# Communication_Interfaces.net
KiCad netlist of a schematic drawn in Altium Designer
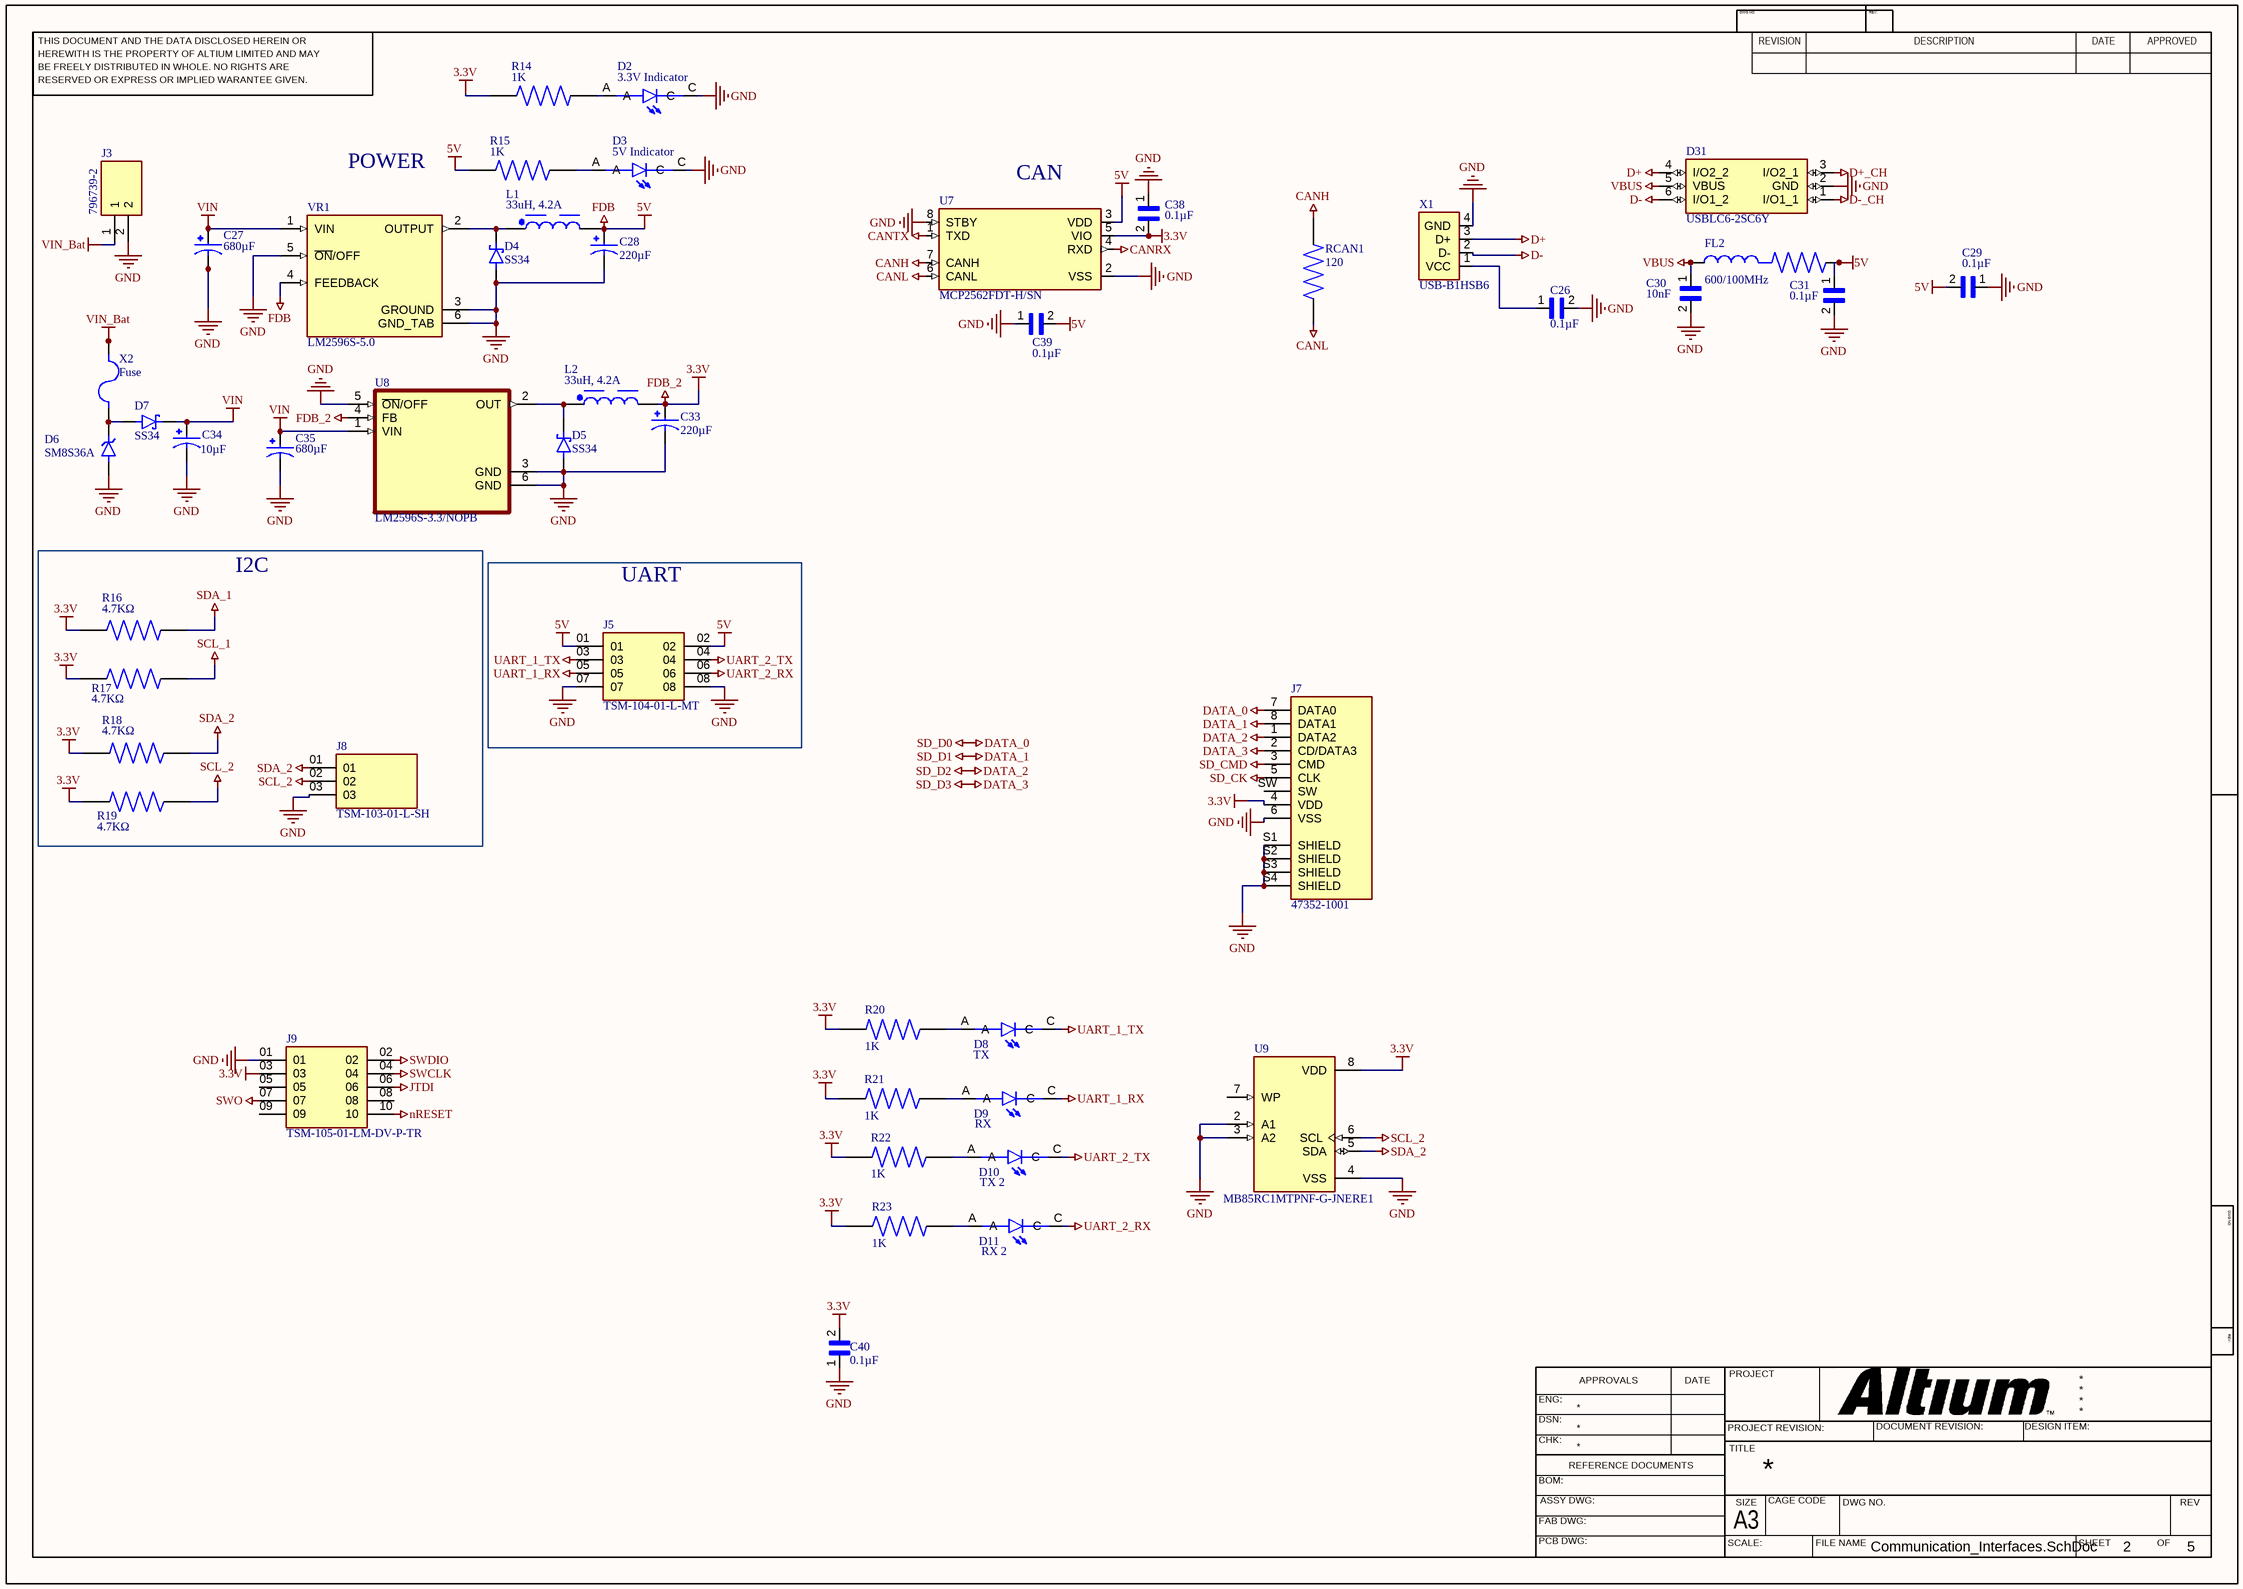
[diagram p0: Communication_Interfaces.SchDoc]

(export (version "E")
  (design (tool "Eeschema 10.0.6"))
  (components
    (comp (ref "C26")
      (value "0.1µF")
      (footprint "CAPC1608X90N")
      (description "Multilayer Ceramic Capacitors MLCC - SMD/SMT")
      (fields (field (name "MP") "06035C104MAZ2A"))
      (libsource (lib "06035C104MAZ2A") (part "06035C104MAZ2A"))
    )
    (comp (ref "C27")
      (value "680µF")
      (footprint "CAP_EEEFN1E681UV")
      (description "CAP ALUM 680UF 20% 25V SMD")
      (fields (field (name "MF") "Panasonic Electronic Components") (field (name "MP") "EEE-FN1E681UV"))
      (libsource (lib "") (part "EEEFN1E681UV_1"))
    )
    (comp (ref "C28")
      (value "220µF")
      (footprint "CAP_EEEFP1V221AV")
      (description "CAP ALUM 220UF 20% 35V SMD")
      (fields (field (name "MF") "Panasonic Electronic Components") (field (name "MP") "EEE-FP1V221AV"))
      (libsource (lib "EEEFP1V221AV") (part "EEEFP1V221AV"))
    )
    (comp (ref "C29")
      (value "0.1µF")
      (footprint "CAPC1608X90N")
      (description "Multilayer Ceramic Capacitors MLCC - SMD/SMT")
      (fields (field (name "MP") "06035C104MAZ2A"))
      (libsource (lib "") (part "06035C104MAZ2A_2"))
    )
    (comp (ref "C30")
      (value "10nF")
      (footprint "CAPC1608X90N")
      (description "Multilayer Ceramic Capacitors MLCC - SMD/SMT")
      (fields (field (name "MP") "06035C104MAZ2A"))
      (libsource (lib "") (part "06035C104MAZ2A_3"))
    )
    (comp (ref "C31")
      (value "0.1µF")
      (footprint "CAPC1608X90N")
      (description "Multilayer Ceramic Capacitors MLCC - SMD/SMT")
      (fields (field (name "MP") "06035C104MAZ2A"))
      (libsource (lib "") (part "06035C104MAZ2A_3"))
    )
    (comp (ref "C33")
      (value "220µF")
      (footprint "CAP_EEEFP1V221AV")
      (description "CAP ALUM 220UF 20% 35V SMD")
      (fields (field (name "MF") "Panasonic Electronic Components") (field (name "MP") "EEE-FP1V221AV"))
      (libsource (lib "") (part "EEEFP1V221AV_1"))
    )
    (comp (ref "C34")
      (value "10µF")
      (footprint "CAPPRD500W50D500H1100")
      (description "10ÂµF 25V Aluminum Electrolytic Capacitors Radial, Can 2000 Hrs @ 85Â°C")
      (fields (field (name "MF") "Panasonic") (field (name "MP") "ECEA1EN100UB"))
      (libsource (lib "ECEA1EN100UB") (part "ECEA1EN100UB"))
    )
    (comp (ref "C35")
      (value "680µF")
      (footprint "CAP_EEEFN1E681UV")
      (description "CAP ALUM 680UF 20% 25V SMD")
      (fields (field (name "MF") "Panasonic Electronic Components") (field (name "MP") "EEE-FN1E681UV"))
      (libsource (lib "EEEFN1E681UV") (part "EEEFN1E681UV"))
    )
    (comp (ref "C38")
      (value "0.1µF")
      (footprint "CAPC1608X90N")
      (description "Multilayer Ceramic Capacitors MLCC - SMD/SMT")
      (fields (field (name "MP") "06035C104MAZ2A"))
      (libsource (lib "") (part "06035C104MAZ2A_3"))
    )
    (comp (ref "C39")
      (value "0.1µF")
      (footprint "CAPC1608X90N")
      (description "Multilayer Ceramic Capacitors MLCC - SMD/SMT")
      (fields (field (name "MP") "06035C104MAZ2A"))
      (libsource (lib "06035C104MAZ2A") (part "06035C104MAZ2A"))
    )
    (comp (ref "C40")
      (value "0.1µF")
      (footprint "CAPC1608X90N")
      (description "Multilayer Ceramic Capacitors MLCC - SMD/SMT")
      (fields (field (name "MP") "06035C104MAZ2A"))
      (libsource (lib "") (part "06035C104MAZ2A_1"))
    )
    (comp (ref "D2")
      (value "3.3V Indicator")
      (footprint "LEDC2012X70N")
      (description "LED Uni-Color Green 4-Pin Chip 0805 T/R")
      (fields (field (name "MP") "597-3305-607F"))
      (libsource (lib "597-3305-607F") (part "597-3305-607F"))
    )
    (comp (ref "D3")
      (value "5V Indicator")
      (footprint "LEDC2012X70N")
      (description "LED Uni-Color Green 4-Pin Chip 0805 T/R")
      (fields (field (name "MP") "597-3305-607F"))
      (libsource (lib "597-3305-607F") (part "597-3305-607F"))
    )
    (comp (ref "D4")
      (value "SS34")
      (footprint "DIO_SS34")
      (description "3A, 40V, Schottky Rectifier")
      (fields (field (name "MF") "Taiwan Semiconductor"))
      (libsource (lib "SS34") (part "SS34"))
    )
    (comp (ref "D5")
      (value "SS34")
      (footprint "DIO_SS34")
      (description "3A, 40V, Schottky Rectifier")
      (fields (field (name "MF") "Taiwan Semiconductor"))
      (libsource (lib "SS34") (part "SS34"))
    )
    (comp (ref "D6")
      (value "SM8S36A")
      (footprint "TVSP_SM8S36A")
      (libsource (lib "SM8S36A") (part "SM8S36A"))
    )
    (comp (ref "D7")
      (value "SS34")
      (footprint "DIO_SS34")
      (description "3A, 40V, Schottky Rectifier")
      (fields (field (name "MF") "Taiwan Semiconductor"))
      (libsource (lib "SS34 (1)") (part "SS34"))
    )
    (comp (ref "D8")
      (value "TX")
      (footprint "LEDC2012X70N")
      (description "LED Uni-Color Green 4-Pin Chip 0805 T/R")
      (fields (field (name "MP") "597-3305-607F"))
      (libsource (lib "597-3305-607F") (part "597-3305-607F"))
    )
    (comp (ref "D9")
      (value "RX")
      (footprint "LEDC2012X70N")
      (description "LED Uni-Color Green 4-Pin Chip 0805 T/R")
      (fields (field (name "MP") "597-3305-607F"))
      (libsource (lib "597-3305-607F") (part "597-3305-607F"))
    )
    (comp (ref "D10")
      (value "TX 2")
      (footprint "LEDC2012X70N")
      (description "LED Uni-Color Green 4-Pin Chip 0805 T/R")
      (fields (field (name "MP") "597-3305-607F"))
      (libsource (lib "597-3305-607F") (part "597-3305-607F"))
    )
    (comp (ref "D11")
      (value "RX 2")
      (footprint "LEDC2012X70N")
      (description "LED Uni-Color Green 4-Pin Chip 0805 T/R")
      (fields (field (name "MP") "597-3305-607F"))
      (libsource (lib "597-3305-607F") (part "597-3305-607F"))
    )
    (comp (ref "D31")
      (value "USBLC6-2SC6Y")
      (footprint "SOT95P280X145-6N")
      (description "17V Clamp 5A (8/20µs) Ipp Tvs Diode Surface Mount SOT-23-6")
      (fields (field (name "MF") "STMicroelectronics"))
      (libsource (lib "USBLC6-2SC6Y") (part "USBLC6-2SC6Y"))
    )
    (comp (ref "FL2")
      (value "600/100MHz")
      (footprint "BEADC1608X95N")
      (description "600 Ohms @ 100MHz 1 Ferrite Bead 0603 _1608 Metric_ 700mA")
      (fields (field (name "MF") "Murata") (field (name "MP") "BLM18DN601SZ1D"))
      (libsource (lib "BLM18DN601SZ1DA") (part "BLM18DN601SZ1D"))
    )
    (comp (ref "J3")
      (value "796739-2")
      (footprint "TE_796739-2")
      (description "Conn Terminal Block F 2 POS 9.53mm Solder RA Thru-Hole 32A/Contact")
      (fields (field (name "MF") "TE Connectivity"))
      (libsource (lib "796739-2") (part "796739-2"))
    )
    (comp (ref "J5")
      (value "TSM-104-01-L-MT")
      (footprint "SAMTEC_TSM-104-01-L-MT")
      (description "TSM Series .100 Surface Mount Terminal Strip")
      (fields (field (name "MF") "Samtec"))
      (libsource (lib "TSM-104-01-L-MT") (part "TSM-104-01-L-MT"))
    )
    (comp (ref "J7")
      (value "47352-1001")
      (footprint "MOLEX_47352-1001")
      (description "8 (6 + 2) Position Card Connector Secure Digital - microSDâ„¢ Surface Mount, Right Angle Gold")
      (fields (field (name "MP") "473521001") (field (name "MF") "Molex"))
      (libsource (lib "47352-1001") (part "47352-1001"))
    )
    (comp (ref "J8")
      (value "TSM-103-01-L-SH")
      (footprint "SAMTEC_TSM-103-01-L-SH")
      (fields (field (name "MF") "Samtec Inc."))
      (libsource (lib "TSM-103-01-L-SH (1)") (part "TSM-103-01-L-SH"))
    )
    (comp (ref "J9")
      (value "TSM-105-01-LM-DV-P-TR")
      (footprint "SAMTEC_TSM-105-01-LM-DV-P-TR")
      (description "TSM - Samtec 2.54mm Dual Row Vertical Surface Mount Header 5.84mm Post Height (01) - Fast Stock")
      (fields (field (name "MF") "Samtec"))
      (libsource (lib "TSM-105-01-LM-DV-P-TR") (part "TSM-105-01-LM-DV-P-TR"))
    )
    (comp (ref "L1")
      (value "33uH, 4.2A")
      (footprint "WE-PD_1210")
      (description "WE-PD SMT Power Inductor, size 1210, 33uH, 4.2A, 45mOhm")
      (fields
        (field (name "MANUFACTURER PART NUMBER") "7447709330")
        (field (name "MANUFACTURER") "Wurth Elektronik")
      )
      (libsource (lib "Altium_WE-PD_rev22g") (part "7447709330"))
    )
    (comp (ref "L2")
      (value "33uH, 4.2A")
      (footprint "WE-PD_1210")
      (description "WE-PD SMT Power Inductor, size 1210, 33uH, 4.2A, 45mOhm")
      (fields
        (field (name "MANUFACTURER PART NUMBER") "7447709330")
        (field (name "MANUFACTURER") "Wurth Elektronik")
      )
      (libsource (lib "Altium_WE-PD_rev22g") (part "7447709330"))
    )
    (comp (ref "R14")
      (value "1K")
      (footprint "RESC3116X65N")
      (fields (field (name "MF") "Yageo Corporation") (field (name "MP") "RC1206JR071KL"))
      (libsource (lib "RC1206JR-071KL") (part "RC1206JR-071KL"))
    )
    (comp (ref "R15")
      (value "1K")
      (footprint "RESC3116X65N")
      (fields (field (name "MF") "Yageo Corporation") (field (name "MP") "RC1206JR071KL"))
      (libsource (lib "RC1206JR-071KL") (part "RC1206JR-071KL"))
    )
    (comp (ref "R16")
      (value "4.7KΩ")
      (footprint "RES_ERJS06J472V")
      (fields (field (name "MP") "ERJS06J472V"))
      (libsource (lib "ERJS06J472V") (part "ERJS06J472V"))
    )
    (comp (ref "R17")
      (value "4.7KΩ")
      (footprint "RES_ERJS06J472V")
      (fields (field (name "MP") "ERJS06J472V"))
      (libsource (lib "ERJS06J472V") (part "ERJS06J472V"))
    )
    (comp (ref "R18")
      (value "4.7KΩ")
      (footprint "RES_ERJS06J472V")
      (fields (field (name "MP") "ERJS06J472V"))
      (libsource (lib "ERJS06J472V") (part "ERJS06J472V"))
    )
    (comp (ref "R19")
      (value "4.7KΩ")
      (footprint "RES_ERJS06J472V")
      (fields (field (name "MP") "ERJS06J472V"))
      (libsource (lib "ERJS06J472V") (part "ERJS06J472V"))
    )
    (comp (ref "R20")
      (value "1K")
      (footprint "RESC3116X65N")
      (fields (field (name "MF") "Yageo Corporation") (field (name "MP") "RC1206JR071KL"))
      (libsource (lib "RC1206JR-071KL") (part "RC1206JR-071KL"))
    )
    (comp (ref "R21")
      (value "1K")
      (footprint "RESC3116X65N")
      (fields (field (name "MF") "Yageo Corporation") (field (name "MP") "RC1206JR071KL"))
      (libsource (lib "RC1206JR-071KL") (part "RC1206JR-071KL"))
    )
    (comp (ref "R22")
      (value "1K")
      (footprint "RESC3116X65N")
      (fields (field (name "MF") "Yageo Corporation") (field (name "MP") "RC1206JR071KL"))
      (libsource (lib "RC1206JR-071KL") (part "RC1206JR-071KL"))
    )
    (comp (ref "R23")
      (value "1K")
      (footprint "RESC3116X65N")
      (fields (field (name "MF") "Yageo Corporation") (field (name "MP") "RC1206JR071KL"))
      (libsource (lib "RC1206JR-071KL") (part "RC1206JR-071KL"))
    )
    (comp (ref "RCAN1")
      (value "120")
      (footprint "RESC3116X65N")
      (fields (field (name "MP") "AA1206JR-07470RL"))
      (libsource (lib "AA1206JR-07470RL") (part "AA1206JR-07470RL"))
    )
    (comp (ref "U7")
      (value "MCP2562FDT-H/SN")
      (footprint "SOIC127P600X175-8N")
      (description "CAN Flexible Data Rate Transceiver ¦ Microchip Technology Inc. MCP2562FDT-H/SN")
      (fields (field (name "MF") "Microchip"))
      (libsource (lib "MCP2562FDT-H_SN") (part "MCP2562FDT-H/SN"))
    )
    (comp (ref "U8")
      (value "LM2596S-3.3/NOPB")
      (footprint "VREG_LM2596S-3.3/NOPB")
      (libsource (lib "LM2596S-3.3_NOPB") (part "LM2596S-3.3/NOPB"))
    )
    (comp (ref "U9")
      (value "MB85RC1MTPNF-G-JNERE1")
      (footprint "SOIC127P600X175-8N")
      (description "FRAM _Ferroelectric RAM_ Memory IC 1Mb _128K x 8_ IÂ²C 3.4MHz 130ns 8-SOP")
      (fields (field (name "MF") "Fujitsu Electronics"))
      (libsource (lib "MB85RC1MTPNF-G-JNERE1") (part "MB85RC1MTPNF-G-JNERE1"))
    )
    (comp (ref "VR1")
      (value "LM2596S-5.0")
      (footprint "TO170P1524X483-6N")
      (description "SIMPLE SWITCHER&reg; 4.5V to 40V, 3A Low Component Count Step-Down Regulator")
      (fields (field (name "MP") "LM2596S-5.0/NOPB") (field (name "MF") "Texas Instruments"))
      (libsource (lib "LM2596S-5.0") (part "LM2596S-5.0"))
    )
    (comp (ref "X1")
      (value "USB-B1HSB6")
      (footprint "OST_USB-B1HSB6")
      (description "USB-B (USB TYPE-B) - Receptacle Connector 4 Position Through Hole, Right Angle")
      (fields (field (name "MF") "On Shore"))
      (libsource (lib "USB-B1HSB6") (part "USB-B1HSB6"))
    )
    (comp (ref "X2")
      (value "Fuse")
      (footprint "FUSE_3522-2")
      (fields (field (name "MF") "{'manufacturer': u'Keystone Electronics'}") (field (name "MP") "3522-2"))
      (libsource (lib "3522-2") (part "3522-2"))
    )
  )
  (nets
    (net (code "1") (name "3.3V") (class "Default")
      (node (ref "C33") (pin "1") (pinfunction "1_1") (pintype "passive"))
      (node (ref "C38") (pin "2") (pinfunction "2_2") (pintype "passive"))
      (node (ref "C40") (pin "2") (pinfunction "2_2") (pintype "passive"))
      (node (ref "J7") (pin "4") (pinfunction "VDD_4") (pintype "passive"))
      (node (ref "J9") (pin "03") (pinfunction "03_03") (pintype "passive"))
      (node (ref "L2") (pin "2") (pinfunction "2_2") (pintype "passive"))
      (node (ref "R14") (pin "1") (pinfunction "1_1") (pintype "passive"))
      (node (ref "R16") (pin "2") (pinfunction "2_2") (pintype "passive"))
      (node (ref "R17") (pin "1") (pinfunction "1_1") (pintype "passive"))
      (node (ref "R18") (pin "2") (pinfunction "2_2") (pintype "passive"))
      (node (ref "R19") (pin "1") (pinfunction "1_1") (pintype "passive"))
      (node (ref "R20") (pin "1") (pinfunction "1_1") (pintype "passive"))
      (node (ref "R21") (pin "1") (pinfunction "1_1") (pintype "passive"))
      (node (ref "R22") (pin "1") (pinfunction "1_1") (pintype "passive"))
      (node (ref "R23") (pin "1") (pinfunction "1_1") (pintype "passive"))
      (node (ref "U7") (pin "5") (pinfunction "VIO_5") (pintype "power_in"))
      (node (ref "U8") (pin "4") (pinfunction "FB_4") (pintype "input"))
      (node (ref "U9") (pin "8") (pinfunction "VDD_8") (pintype "power_in"))
    )
    (net (code "2") (name "5V") (class "Default")
      (node (ref "C28") (pin "1") (pinfunction "1_1") (pintype "passive"))
      (node (ref "C29") (pin "2") (pinfunction "2_2") (pintype "passive"))
      (node (ref "C31") (pin "1") (pinfunction "1_1") (pintype "passive"))
      (node (ref "C39") (pin "2") (pinfunction "2_2") (pintype "passive"))
      (node (ref "FL2") (pin "2") (pinfunction "2_2") (pintype "passive"))
      (node (ref "J5") (pin "01") (pinfunction "01_01") (pintype "passive"))
      (node (ref "J5") (pin "02") (pinfunction "02_02") (pintype "passive"))
      (node (ref "L1") (pin "2") (pinfunction "2_2") (pintype "passive"))
      (node (ref "R15") (pin "1") (pinfunction "1_1") (pintype "passive"))
      (node (ref "U7") (pin "3") (pinfunction "VDD_3") (pintype "power_in"))
      (node (ref "VR1") (pin "4") (pinfunction "FEEDBACK_4") (pintype "input"))
    )
    (net (code "3") (name "CANH") (class "Default")
      (node (ref "RCAN1") (pin "2") (pinfunction "2_2") (pintype "passive"))
      (node (ref "U7") (pin "7") (pinfunction "CANH_7") (pintype "input"))
    )
    (net (code "4") (name "CANL") (class "Default")
      (node (ref "RCAN1") (pin "1") (pinfunction "1_1") (pintype "passive"))
      (node (ref "U7") (pin "6") (pinfunction "CANL_6") (pintype "input"))
    )
    (net (code "5") (name "CANRX") (class "Default")
      (node (ref "U7") (pin "4") (pinfunction "RXD_4") (pintype "output"))
    )
    (net (code "6") (name "CANTX") (class "Default")
      (node (ref "U7") (pin "1") (pinfunction "TXD_1") (pintype "input"))
    )
    (net (code "7") (name "D+") (class "Default")
      (node (ref "D31") (pin "4") (pinfunction "I/O2_2_4") (pintype "bidirectional"))
      (node (ref "X1") (pin "3") (pinfunction "D+_3") (pintype "bidirectional"))
    )
    (net (code "8") (name "D+_CH") (class "Default")
      (node (ref "D31") (pin "3") (pinfunction "I/O2_1_3") (pintype "bidirectional"))
    )
    (net (code "9") (name "D-") (class "Default")
      (node (ref "D31") (pin "6") (pinfunction "I/O1_2_6") (pintype "bidirectional"))
      (node (ref "X1") (pin "2") (pinfunction "D-_2") (pintype "bidirectional"))
    )
    (net (code "10") (name "D-_CH") (class "Default")
      (node (ref "D31") (pin "1") (pinfunction "I/O1_1_1") (pintype "bidirectional"))
    )
    (net (code "11") (name "DATA_0") (class "Default")
      (node (ref "J7") (pin "7") (pinfunction "DATA0_7") (pintype "passive"))
    )
    (net (code "12") (name "DATA_1") (class "Default")
      (node (ref "J7") (pin "8") (pinfunction "DATA1_8") (pintype "passive"))
    )
    (net (code "13") (name "DATA_2") (class "Default")
      (node (ref "J7") (pin "1") (pinfunction "DATA2_1") (pintype "passive"))
    )
    (net (code "14") (name "DATA_3") (class "Default")
      (node (ref "J7") (pin "2") (pinfunction "CD/DATA3_2") (pintype "passive"))
    )
    (net (code "15") (name "GND") (class "Default")
      (node (ref "C26") (pin "2") (pinfunction "2_2") (pintype "passive"))
      (node (ref "C27") (pin "2") (pinfunction "2_2") (pintype "passive"))
      (node (ref "C28") (pin "2") (pinfunction "2_2") (pintype "passive"))
      (node (ref "C29") (pin "1") (pinfunction "1_1") (pintype "passive"))
      (node (ref "C30") (pin "2") (pinfunction "2_2") (pintype "passive"))
      (node (ref "C31") (pin "2") (pinfunction "2_2") (pintype "passive"))
      (node (ref "C33") (pin "2") (pinfunction "2_2") (pintype "passive"))
      (node (ref "C34") (pin "N") (pinfunction "N_N") (pintype "passive"))
      (node (ref "C35") (pin "2") (pinfunction "2_2") (pintype "passive"))
      (node (ref "C38") (pin "1") (pinfunction "1_1") (pintype "passive"))
      (node (ref "C39") (pin "1") (pinfunction "1_1") (pintype "passive"))
      (node (ref "C40") (pin "1") (pinfunction "1_1") (pintype "passive"))
      (node (ref "D2") (pin "C") (pinfunction "C_C") (pintype "passive"))
      (node (ref "D3") (pin "C") (pinfunction "C_C") (pintype "passive"))
      (node (ref "D31") (pin "2") (pinfunction "GND_2") (pintype "bidirectional"))
      (node (ref "D4") (pin "A") (pinfunction "A_A") (pintype "passive"))
      (node (ref "D5") (pin "A") (pinfunction "A_A") (pintype "passive"))
      (node (ref "D6") (pin "2") (pinfunction "A_2") (pintype "passive"))
      (node (ref "J3") (pin "2") (pinfunction "2_2") (pintype "passive"))
      (node (ref "J5") (pin "07") (pinfunction "07_07") (pintype "passive"))
      (node (ref "J5") (pin "08") (pinfunction "08_08") (pintype "passive"))
      (node (ref "J7") (pin "6") (pinfunction "VSS_6") (pintype "passive"))
      (node (ref "J7") (pin "S1") (pinfunction "SHIELD_S1") (pintype "passive"))
      (node (ref "J7") (pin "S2") (pinfunction "SHIELD_S2") (pintype "passive"))
      (node (ref "J7") (pin "S3") (pinfunction "SHIELD_S3") (pintype "passive"))
      (node (ref "J7") (pin "S4") (pinfunction "SHIELD_S4") (pintype "passive"))
      (node (ref "J8") (pin "03") (pinfunction "03_03") (pintype "passive"))
      (node (ref "J9") (pin "01") (pinfunction "01_01") (pintype "passive"))
      (node (ref "U7") (pin "2") (pinfunction "VSS_2") (pintype "power_in"))
      (node (ref "U7") (pin "8") (pinfunction "STBY_8") (pintype "input"))
      (node (ref "U8") (pin "3") (pinfunction "GND_3") (pintype "power_in"))
      (node (ref "U8") (pin "5") (pinfunction "~{ON}/OFF_5") (pintype "input"))
      (node (ref "U8") (pin "6") (pinfunction "GND_6") (pintype "power_in"))
      (node (ref "U9") (pin "2") (pinfunction "A1_2") (pintype "input"))
      (node (ref "U9") (pin "3") (pinfunction "A2_3") (pintype "input"))
      (node (ref "U9") (pin "4") (pinfunction "VSS_4") (pintype "power_in"))
      (node (ref "VR1") (pin "3") (pinfunction "GROUND_3") (pintype "power_in"))
      (node (ref "VR1") (pin "5") (pinfunction "~{ON}/OFF_5") (pintype "input"))
      (node (ref "VR1") (pin "6") (pinfunction "GND_TAB_6") (pintype "power_in"))
      (node (ref "X1") (pin "4") (pinfunction "GND_4") (pintype "power_in"))
    )
    (net (code "16") (name "JTDI") (class "Default")
      (node (ref "J9") (pin "06") (pinfunction "06_06") (pintype "passive"))
    )
    (net (code "17") (name "Net-(D2-PadA)") (class "Default")
      (node (ref "D2") (pin "A") (pinfunction "A_A") (pintype "passive"))
      (node (ref "R14") (pin "2") (pinfunction "2_2") (pintype "passive"))
    )
    (net (code "18") (name "Net-(D3-PadA)") (class "Default")
      (node (ref "D3") (pin "A") (pinfunction "A_A") (pintype "passive"))
      (node (ref "R15") (pin "2") (pinfunction "2_2") (pintype "passive"))
    )
    (net (code "19") (name "Net-(D4-K)") (class "Default")
      (node (ref "D4") (pin "C") (pinfunction "K_C") (pintype "passive"))
      (node (ref "L1") (pin "1") (pinfunction "1_1") (pintype "passive"))
      (node (ref "VR1") (pin "2") (pinfunction "OUTPUT_2") (pintype "output"))
    )
    (net (code "20") (name "Net-(D5-K)") (class "Default")
      (node (ref "D5") (pin "C") (pinfunction "K_C") (pintype "passive"))
      (node (ref "L2") (pin "1") (pinfunction "1_1") (pintype "passive"))
      (node (ref "U8") (pin "2") (pinfunction "OUT_2") (pintype "output"))
    )
    (net (code "21") (name "Net-(D6-K)") (class "Default")
      (node (ref "D6") (pin "1") (pinfunction "K_1") (pintype "passive"))
      (node (ref "D7") (pin "A") (pinfunction "A_A") (pintype "passive"))
      (node (ref "X2") (pin "1A") (pinfunction "1_1A") (pintype "passive"))
      (node (ref "X2") (pin "1B") (pinfunction "1_1B") (pintype "passive"))
    )
    (net (code "22") (name "Net-(D8-PadA)") (class "Default")
      (node (ref "D8") (pin "A") (pinfunction "A_A") (pintype "passive"))
      (node (ref "R20") (pin "2") (pinfunction "2_2") (pintype "passive"))
    )
    (net (code "23") (name "Net-(D9-PadA)") (class "Default")
      (node (ref "D9") (pin "A") (pinfunction "A_A") (pintype "passive"))
      (node (ref "R21") (pin "2") (pinfunction "2_2") (pintype "passive"))
    )
    (net (code "24") (name "Net-(D10-PadA)") (class "Default")
      (node (ref "D10") (pin "A") (pinfunction "A_A") (pintype "passive"))
      (node (ref "R22") (pin "2") (pinfunction "2_2") (pintype "passive"))
    )
    (net (code "25") (name "Net-(D11-PadA)") (class "Default")
      (node (ref "D11") (pin "A") (pinfunction "A_A") (pintype "passive"))
      (node (ref "R23") (pin "2") (pinfunction "2_2") (pintype "passive"))
    )
    (net (code "26") (name "Net-(X1-VCC)") (class "Default")
      (node (ref "C26") (pin "1") (pinfunction "1_1") (pintype "passive"))
      (node (ref "X1") (pin "1") (pinfunction "VCC_1") (pintype "power_in"))
    )
    (net (code "27") (name "SCL_1") (class "Default")
      (node (ref "R17") (pin "2") (pinfunction "2_2") (pintype "passive"))
    )
    (net (code "28") (name "SCL_2") (class "Default")
      (node (ref "J8") (pin "02") (pinfunction "02_02") (pintype "passive"))
      (node (ref "R19") (pin "2") (pinfunction "2_2") (pintype "passive"))
      (node (ref "U9") (pin "6") (pinfunction "SCL_6") (pintype "input"))
    )
    (net (code "29") (name "SDA_1") (class "Default")
      (node (ref "R16") (pin "1") (pinfunction "1_1") (pintype "passive"))
    )
    (net (code "30") (name "SDA_2") (class "Default")
      (node (ref "J8") (pin "01") (pinfunction "01_01") (pintype "passive"))
      (node (ref "R18") (pin "1") (pinfunction "1_1") (pintype "passive"))
      (node (ref "U9") (pin "5") (pinfunction "SDA_5") (pintype "bidirectional"))
    )
    (net (code "31") (name "SD_CK") (class "Default")
      (node (ref "J7") (pin "5") (pinfunction "CLK_5") (pintype "passive"))
    )
    (net (code "32") (name "SD_CMD") (class "Default")
      (node (ref "J7") (pin "3") (pinfunction "CMD_3") (pintype "passive"))
    )
    (net (code "33") (name "SWCLK") (class "Default")
      (node (ref "J9") (pin "04") (pinfunction "04_04") (pintype "passive"))
    )
    (net (code "34") (name "SWDIO") (class "Default")
      (node (ref "J9") (pin "02") (pinfunction "02_02") (pintype "passive"))
    )
    (net (code "35") (name "SWO") (class "Default")
      (node (ref "J9") (pin "07") (pinfunction "07_07") (pintype "passive"))
    )
    (net (code "36") (name "UART_1_RX") (class "Default")
      (node (ref "D9") (pin "C") (pinfunction "C_C") (pintype "passive"))
      (node (ref "J5") (pin "05") (pinfunction "05_05") (pintype "passive"))
    )
    (net (code "37") (name "UART_1_TX") (class "Default")
      (node (ref "D8") (pin "C") (pinfunction "C_C") (pintype "passive"))
      (node (ref "J5") (pin "03") (pinfunction "03_03") (pintype "passive"))
    )
    (net (code "38") (name "UART_2_RX") (class "Default")
      (node (ref "D11") (pin "C") (pinfunction "C_C") (pintype "passive"))
      (node (ref "J5") (pin "06") (pinfunction "06_06") (pintype "passive"))
    )
    (net (code "39") (name "UART_2_TX") (class "Default")
      (node (ref "D10") (pin "C") (pinfunction "C_C") (pintype "passive"))
      (node (ref "J5") (pin "04") (pinfunction "04_04") (pintype "passive"))
    )
    (net (code "40") (name "VBUS") (class "Default")
      (node (ref "C30") (pin "1") (pinfunction "1_1") (pintype "passive"))
      (node (ref "D31") (pin "5") (pinfunction "VBUS_5") (pintype "bidirectional"))
      (node (ref "FL2") (pin "1") (pinfunction "1_1") (pintype "passive"))
    )
    (net (code "41") (name "VIN") (class "Default")
      (node (ref "C27") (pin "1") (pinfunction "1_1") (pintype "passive"))
      (node (ref "C34") (pin "P") (pinfunction "P_P") (pintype "passive"))
      (node (ref "C35") (pin "1") (pinfunction "1_1") (pintype "passive"))
      (node (ref "D7") (pin "C") (pinfunction "K_C") (pintype "passive"))
      (node (ref "U8") (pin "1") (pinfunction "VIN_1") (pintype "input"))
      (node (ref "VR1") (pin "1") (pinfunction "VIN_1") (pintype "input"))
    )
    (net (code "42") (name "VIN_Bat") (class "Default")
      (node (ref "J3") (pin "1") (pinfunction "1_1") (pintype "passive"))
      (node (ref "X2") (pin "2A") (pinfunction "2_2A") (pintype "passive"))
      (node (ref "X2") (pin "2B") (pinfunction "2_2B") (pintype "passive"))
    )
    (net (code "43") (name "nRESET") (class "Default")
      (node (ref "J9") (pin "10") (pinfunction "10_10") (pintype "passive"))
    )
    (net (code "44") (name "unconnected-(J7-PadSW)") (class "Default")
      (node (ref "J7") (pin "SW") (pinfunction "SW_SW") (pintype "passive"))
    )
    (net (code "45") (name "unconnected-(J9-Pad05)") (class "Default")
      (node (ref "J9") (pin "05") (pinfunction "05_05") (pintype "passive"))
    )
    (net (code "46") (name "unconnected-(J9-Pad08)") (class "Default")
      (node (ref "J9") (pin "08") (pinfunction "08_08") (pintype "passive"))
    )
    (net (code "47") (name "unconnected-(J9-Pad09)") (class "Default")
      (node (ref "J9") (pin "09") (pinfunction "09_09") (pintype "passive"))
    )
    (net (code "48") (name "unconnected-(U9-WP-Pad7)") (class "Default")
      (node (ref "U9") (pin "7") (pinfunction "WP_7") (pintype "input"))
    )
  )
)
